# KillAutoSystem.net
KiCad netlist of a schematic drawn in Altium Designer
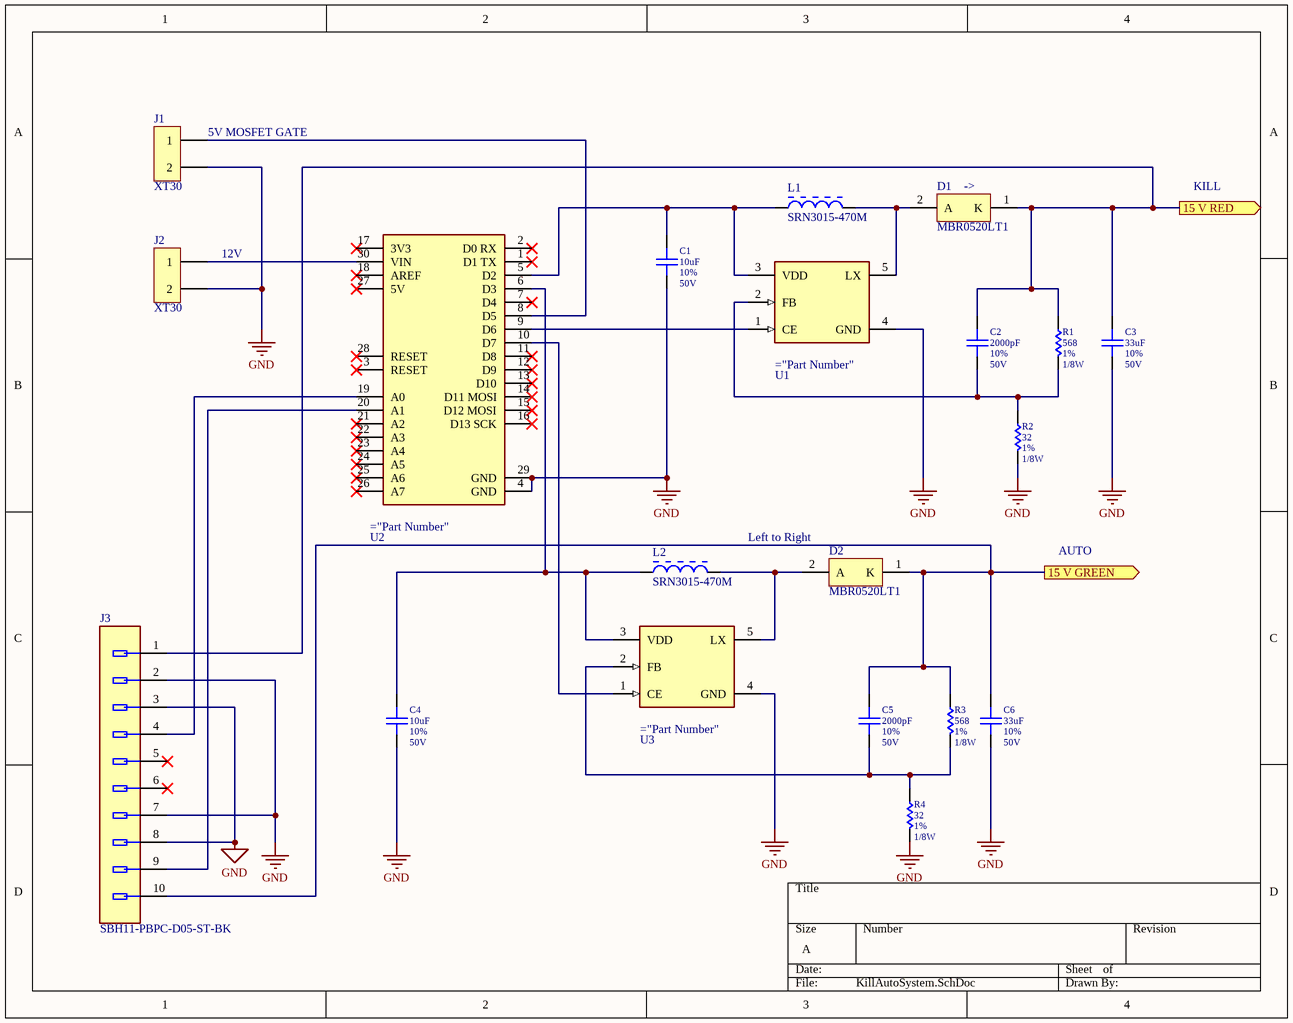
[diagram p0: KillAutoSystem.SchDoc]

(export (version "E")
  (design (tool "Eeschema 10.0.6"))
  (components
    (comp (ref "C1")
      (value "Ceramic Capacitor")
      (footprint "Component 0805")
      (fields
        (field (name "CAPACITANCE") "10uF")
        (field (name "TOLERANCE") "10%")
        (field (name "VOLTAGE") "50V")
      )
      (libsource (lib "MechatronicsSCH") (part "Capacitor, Ceramic"))
    )
    (comp (ref "C2")
      (value "Ceramic Capacitor")
      (footprint "Component 0805")
      (fields
        (field (name "CAPACITANCE") "2000pF")
        (field (name "TOLERANCE") "10%")
        (field (name "VOLTAGE") "50V")
      )
      (libsource (lib "MechatronicsSCH") (part "Capacitor, Ceramic"))
    )
    (comp (ref "C3")
      (value "Ceramic Capacitor")
      (footprint "Component 0805")
      (fields
        (field (name "CAPACITANCE") "33uF")
        (field (name "TOLERANCE") "10%")
        (field (name "VOLTAGE") "50V")
      )
      (libsource (lib "MechatronicsSCH") (part "Capacitor, Ceramic"))
    )
    (comp (ref "C4")
      (value "Ceramic Capacitor")
      (footprint "Component 0805")
      (fields
        (field (name "CAPACITANCE") "10uF")
        (field (name "TOLERANCE") "10%")
        (field (name "VOLTAGE") "50V")
      )
      (libsource (lib "MechatronicsSCH") (part "Capacitor, Ceramic"))
    )
    (comp (ref "C5")
      (value "Ceramic Capacitor")
      (footprint "Component 0805")
      (fields
        (field (name "CAPACITANCE") "2000pF")
        (field (name "TOLERANCE") "10%")
        (field (name "VOLTAGE") "50V")
      )
      (libsource (lib "MechatronicsSCH") (part "Capacitor, Ceramic"))
    )
    (comp (ref "C6")
      (value "Ceramic Capacitor")
      (footprint "Component 0805")
      (fields
        (field (name "CAPACITANCE") "33uF")
        (field (name "TOLERANCE") "10%")
        (field (name "VOLTAGE") "50V")
      )
      (libsource (lib "MechatronicsSCH") (part "Capacitor, Ceramic"))
    )
    (comp (ref "D1")
      (value "MBR0520LT1")
      (footprint "ONSC-SOD-123-2-425-04_V")
      (description "Schottky Power Rectifier, 2-Pin SOD-123, Tape and Reel")
      (fields (field (name "MANUFACTURER") "On Semiconductor"))
      (libsource (lib "MechatronicsSCH") (part "MBR0520LT1"))
    )
    (comp (ref "D2")
      (value "MBR0520LT1")
      (footprint "ONSC-SOD-123-2-425-04_V")
      (description "Schottky Power Rectifier, 2-Pin SOD-123, Tape and Reel")
      (fields (field (name "MANUFACTURER") "On Semiconductor"))
      (libsource (lib "MechatronicsSCH") (part "MBR0520LT1"))
    )
    (comp (ref "J1")
      (value "XT30")
      (footprint "Connector, XT30")
      (libsource (lib "MechatronicsSCH") (part "Connector, XT30"))
    )
    (comp (ref "J2")
      (value "XT30")
      (footprint "Connector, XT30")
      (libsource (lib "MechatronicsSCH") (part "Connector, XT30"))
    )
    (comp (ref "J3")
      (value "Conn_Sullins_Headers_SBH11-PBPC-D05-ST-BK_eec")
      (footprint "Sullins_Headers_SBH11-PBPC-D05-ST-BK_0")
      (description "CONN 10 Positions Header Connector 0.100\" (2.54mm) Through Hole Gold")
      (fields
        (field (name "MANUFACTURER") "Sullins Headers")
        (field (name "DIGIKEY PART NUMBER") "S9169-ND")
        (field (name "PART NUMBER") "SBH11-PBPC-D05-ST-BK")
      )
      (libsource (lib "MechatronicsSCH") (part "Conn_Sullins_Headers_SBH11-PBPC-D05-ST-BK_eec"))
    )
    (comp (ref "L1")
      (value "SRN3015-470M")
      (footprint "BOUR-SRN3015-2_V")
      (fields (field (name "MANUFACTURER") "Bourns"))
      (libsource (lib "MechatronicsSCH") (part "SRN3015-470M"))
    )
    (comp (ref "L2")
      (value "SRN3015-470M")
      (footprint "BOUR-SRN3015-2_V")
      (fields (field (name "MANUFACTURER") "Bourns"))
      (libsource (lib "MechatronicsSCH") (part "SRN3015-470M"))
    )
    (comp (ref "R1")
      (value "Resistor")
      (footprint "Component 0805")
      (description "Thick Film Resistors - SMD 1/16watt 1%")
      (fields (field (name "RESISTANCE") "568") (field (name "TOLERANCE") "1%") (field (name "POWER") "1/8W"))
      (libsource (lib "MechatronicsSCH") (part "Resistor"))
    )
    (comp (ref "R2")
      (value "Resistor")
      (footprint "Component 0805")
      (description "Thick Film Resistors - SMD 1/16watt 1%")
      (fields (field (name "RESISTANCE") "32") (field (name "TOLERANCE") "1%") (field (name "POWER") "1/8W"))
      (libsource (lib "MechatronicsSCH") (part "Resistor"))
    )
    (comp (ref "R3")
      (value "Resistor")
      (footprint "Component 0805")
      (description "Thick Film Resistors - SMD 1/16watt 1%")
      (fields (field (name "RESISTANCE") "568") (field (name "TOLERANCE") "1%") (field (name "POWER") "1/8W"))
      (libsource (lib "MechatronicsSCH") (part "Resistor"))
    )
    (comp (ref "R4")
      (value "Resistor")
      (footprint "Component 0805")
      (description "Thick Film Resistors - SMD 1/16watt 1%")
      (fields (field (name "RESISTANCE") "32") (field (name "TOLERANCE") "1%") (field (name "POWER") "1/8W"))
      (libsource (lib "MechatronicsSCH") (part "Resistor"))
    )
    (comp (ref "U1")
      (value "NCP1403SNT1G")
      (footprint "ON_Semi_483_0")
      (description "Boost Converter")
      (libsource (lib "MechatronicsSCH") (part "NCP1403SNT1G"))
    )
    (comp (ref "U2")
      (value "Arduino_Nano_3.0")
      (footprint "Arduino_Arduino_Nano_3.0_0")
      (libsource (lib "MechatronicsSCH") (part "Arduino_Nano_3.0"))
    )
    (comp (ref "U3")
      (value "NCP1403SNT1G")
      (footprint "ON_Semi_483_0")
      (description "Boost Converter")
      (libsource (lib "MechatronicsSCH") (part "NCP1403SNT1G"))
    )
  )
  (nets
    (net (code "1") (name "/15 V GREEN") (class "Default")
      (node (ref "C5") (pin "1") (pinfunction "1_1") (pintype "passive"))
      (node (ref "C6") (pin "1") (pinfunction "1_1") (pintype "passive"))
      (node (ref "D2") (pin "1") (pinfunction "K_1") (pintype "passive"))
      (node (ref "J3") (pin "10") (pinfunction "10_10") (pintype "passive"))
      (node (ref "R3") (pin "1") (pinfunction "1_1") (pintype "passive"))
    )
    (net (code "2") (name "/15 V RED") (class "Default")
      (node (ref "C2") (pin "1") (pinfunction "1_1") (pintype "passive"))
      (node (ref "C3") (pin "1") (pinfunction "1_1") (pintype "passive"))
      (node (ref "D1") (pin "1") (pinfunction "K_1") (pintype "passive"))
      (node (ref "J3") (pin "1") (pinfunction "1_1") (pintype "passive"))
      (node (ref "R1") (pin "1") (pinfunction "1_1") (pintype "passive"))
    )
    (net (code "3") (name "GND") (class "Default")
      (node (ref "C1") (pin "2") (pinfunction "2_2") (pintype "passive"))
      (node (ref "C3") (pin "2") (pinfunction "2_2") (pintype "passive"))
      (node (ref "C4") (pin "2") (pinfunction "2_2") (pintype "passive"))
      (node (ref "C6") (pin "2") (pinfunction "2_2") (pintype "passive"))
      (node (ref "J1") (pin "2") (pinfunction "2_2") (pintype "passive"))
      (node (ref "J2") (pin "2") (pinfunction "2_2") (pintype "passive"))
      (node (ref "J3") (pin "2") (pinfunction "2_2") (pintype "passive"))
      (node (ref "J3") (pin "3") (pinfunction "3_3") (pintype "passive"))
      (node (ref "J3") (pin "7") (pinfunction "7_7") (pintype "passive"))
      (node (ref "J3") (pin "8") (pinfunction "8_8") (pintype "passive"))
      (node (ref "R2") (pin "2") (pinfunction "2_2") (pintype "passive"))
      (node (ref "R4") (pin "2") (pinfunction "2_2") (pintype "passive"))
      (node (ref "U1") (pin "4") (pinfunction "GND_4") (pintype "power_in"))
      (node (ref "U2") (pin "29") (pinfunction "GND_29") (pintype "passive"))
      (node (ref "U2") (pin "4") (pinfunction "GND_4") (pintype "passive"))
      (node (ref "U3") (pin "4") (pinfunction "GND_4") (pintype "power_in"))
    )
    (net (code "4") (name "Net-(D1-A)") (class "Default")
      (node (ref "D1") (pin "2") (pinfunction "A_2") (pintype "passive"))
      (node (ref "L1") (pin "2") (pinfunction "2_2") (pintype "passive"))
      (node (ref "U1") (pin "5") (pinfunction "LX_5") (pintype "power_in"))
    )
    (net (code "5") (name "Net-(D2-A)") (class "Default")
      (node (ref "D2") (pin "2") (pinfunction "A_2") (pintype "passive"))
      (node (ref "L2") (pin "2") (pinfunction "2_2") (pintype "passive"))
      (node (ref "U3") (pin "5") (pinfunction "LX_5") (pintype "power_in"))
    )
    (net (code "6") (name "Net-(U1-CE)") (class "Default")
      (node (ref "U1") (pin "1") (pinfunction "CE_1") (pintype "input"))
      (node (ref "U2") (pin "9") (pinfunction "D6_9") (pintype "passive"))
    )
    (net (code "7") (name "Net-(U1-FB)") (class "Default")
      (node (ref "C2") (pin "2") (pinfunction "2_2") (pintype "passive"))
      (node (ref "R1") (pin "2") (pinfunction "2_2") (pintype "passive"))
      (node (ref "R2") (pin "1") (pinfunction "1_1") (pintype "passive"))
      (node (ref "U1") (pin "2") (pinfunction "FB_2") (pintype "input"))
    )
    (net (code "8") (name "Net-(U1-VDD)") (class "Default")
      (node (ref "C1") (pin "1") (pinfunction "1_1") (pintype "passive"))
      (node (ref "L1") (pin "1") (pinfunction "1_1") (pintype "passive"))
      (node (ref "U1") (pin "3") (pinfunction "VDD_3") (pintype "power_in"))
      (node (ref "U2") (pin "5") (pinfunction "D2_5") (pintype "passive"))
    )
    (net (code "9") (name "Net-(U2-A0)") (class "Default")
      (node (ref "J3") (pin "4") (pinfunction "4_4") (pintype "passive"))
      (node (ref "U2") (pin "19") (pinfunction "A0_19") (pintype "passive"))
    )
    (net (code "10") (name "Net-(U2-A1)") (class "Default")
      (node (ref "J3") (pin "9") (pinfunction "9_9") (pintype "passive"))
      (node (ref "U2") (pin "20") (pinfunction "A1_20") (pintype "passive"))
    )
    (net (code "11") (name "Net-(U2-D3)") (class "Default")
      (node (ref "C4") (pin "1") (pinfunction "1_1") (pintype "passive"))
      (node (ref "L2") (pin "1") (pinfunction "1_1") (pintype "passive"))
      (node (ref "U2") (pin "6") (pinfunction "D3_6") (pintype "passive"))
      (node (ref "U3") (pin "3") (pinfunction "VDD_3") (pintype "power_in"))
    )
    (net (code "12") (name "Net-(U2-D5)") (class "Default")
      (node (ref "J1") (pin "1") (pinfunction "1_1") (pintype "passive"))
      (node (ref "U2") (pin "8") (pinfunction "D5_8") (pintype "passive"))
    )
    (net (code "13") (name "Net-(U2-D7)") (class "Default")
      (node (ref "U2") (pin "10") (pinfunction "D7_10") (pintype "passive"))
      (node (ref "U3") (pin "1") (pinfunction "CE_1") (pintype "input"))
    )
    (net (code "14") (name "Net-(U2-VIN)") (class "Default")
      (node (ref "J2") (pin "1") (pinfunction "1_1") (pintype "passive"))
      (node (ref "U2") (pin "30") (pinfunction "VIN_30") (pintype "passive"))
    )
    (net (code "15") (name "Net-(U3-FB)") (class "Default")
      (node (ref "C5") (pin "2") (pinfunction "2_2") (pintype "passive"))
      (node (ref "R3") (pin "2") (pinfunction "2_2") (pintype "passive"))
      (node (ref "R4") (pin "1") (pinfunction "1_1") (pintype "passive"))
      (node (ref "U3") (pin "2") (pinfunction "FB_2") (pintype "input"))
    )
    (net (code "16") (name "unconnected-(J3-Pad5)") (class "Default")
      (node (ref "J3") (pin "5") (pinfunction "5_5") (pintype "passive+no_connect"))
    )
    (net (code "17") (name "unconnected-(J3-Pad6)") (class "Default")
      (node (ref "J3") (pin "6") (pinfunction "6_6") (pintype "passive+no_connect"))
    )
    (net (code "18") (name "unconnected-(U2-3V3-Pad17)") (class "Default")
      (node (ref "U2") (pin "17") (pinfunction "3V3_17") (pintype "passive+no_connect"))
    )
    (net (code "19") (name "unconnected-(U2-5V-Pad27)") (class "Default")
      (node (ref "U2") (pin "27") (pinfunction "5V_27") (pintype "passive+no_connect"))
    )
    (net (code "20") (name "unconnected-(U2-A2-Pad21)") (class "Default")
      (node (ref "U2") (pin "21") (pinfunction "A2_21") (pintype "passive+no_connect"))
    )
    (net (code "21") (name "unconnected-(U2-A3-Pad22)") (class "Default")
      (node (ref "U2") (pin "22") (pinfunction "A3_22") (pintype "passive+no_connect"))
    )
    (net (code "22") (name "unconnected-(U2-A4-Pad23)") (class "Default")
      (node (ref "U2") (pin "23") (pinfunction "A4_23") (pintype "passive+no_connect"))
    )
    (net (code "23") (name "unconnected-(U2-A5-Pad24)") (class "Default")
      (node (ref "U2") (pin "24") (pinfunction "A5_24") (pintype "passive+no_connect"))
    )
    (net (code "24") (name "unconnected-(U2-A6-Pad25)") (class "Default")
      (node (ref "U2") (pin "25") (pinfunction "A6_25") (pintype "passive+no_connect"))
    )
    (net (code "25") (name "unconnected-(U2-A7-Pad26)") (class "Default")
      (node (ref "U2") (pin "26") (pinfunction "A7_26") (pintype "passive+no_connect"))
    )
    (net (code "26") (name "unconnected-(U2-AREF-Pad18)") (class "Default")
      (node (ref "U2") (pin "18") (pinfunction "AREF_18") (pintype "passive+no_connect"))
    )
    (net (code "27") (name "unconnected-(U2-D0_RX-Pad2)") (class "Default")
      (node (ref "U2") (pin "2") (pinfunction "D0_RX_2") (pintype "passive+no_connect"))
    )
    (net (code "28") (name "unconnected-(U2-D1_TX-Pad1)") (class "Default")
      (node (ref "U2") (pin "1") (pinfunction "D1_TX_1") (pintype "passive+no_connect"))
    )
    (net (code "29") (name "unconnected-(U2-D4-Pad7)") (class "Default")
      (node (ref "U2") (pin "7") (pinfunction "D4_7") (pintype "passive+no_connect"))
    )
    (net (code "30") (name "unconnected-(U2-D8-Pad11)") (class "Default")
      (node (ref "U2") (pin "11") (pinfunction "D8_11") (pintype "passive+no_connect"))
    )
    (net (code "31") (name "unconnected-(U2-D9-Pad12)") (class "Default")
      (node (ref "U2") (pin "12") (pinfunction "D9_12") (pintype "passive+no_connect"))
    )
    (net (code "32") (name "unconnected-(U2-D10-Pad13)") (class "Default")
      (node (ref "U2") (pin "13") (pinfunction "D10_13") (pintype "passive+no_connect"))
    )
    (net (code "33") (name "unconnected-(U2-D11_MOSI-Pad14)") (class "Default")
      (node (ref "U2") (pin "14") (pinfunction "D11_MOSI_14") (pintype "passive+no_connect"))
    )
    (net (code "34") (name "unconnected-(U2-D12_MOSI-Pad15)") (class "Default")
      (node (ref "U2") (pin "15") (pinfunction "D12_MOSI_15") (pintype "passive+no_connect"))
    )
    (net (code "35") (name "unconnected-(U2-D13_SCK-Pad16)") (class "Default")
      (node (ref "U2") (pin "16") (pinfunction "D13_SCK_16") (pintype "passive+no_connect"))
    )
    (net (code "36") (name "unconnected-(U2-RESET-Pad3)") (class "Default")
      (node (ref "U2") (pin "3") (pinfunction "RESET_3") (pintype "passive+no_connect"))
    )
    (net (code "37") (name "unconnected-(U2-RESET-Pad28)") (class "Default")
      (node (ref "U2") (pin "28") (pinfunction "RESET_28") (pintype "passive+no_connect"))
    )
  )
)
